# ul_tx_ctrl.net
KiCad netlist of a schematic drawn in Altium Designer
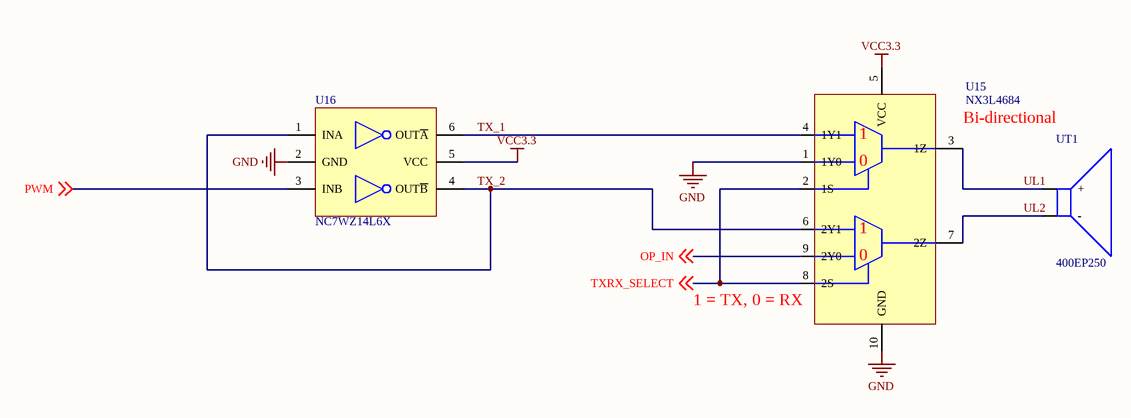
[diagram p0: ul_tx_ctrl.SchDoc]

(export (version "E")
  (design (tool "Eeschema 10.0.6"))
  (components
    (comp (ref "U15")
      (value "NX3L4684")
      (footprint "QFN50P155X200X13-10N")
      (description "IC ANALOG SWITCH SPDT 10XQFN")
      (libsource (lib "opo") (part "NX3L4684"))
    )
    (comp (ref "U16")
      (value "NC7WZ14L6X")
      (footprint "NC7WZ14L6X")
      (description "1 uA supply current, 50 mA output current, Dual inverter")
      (fields (field (name "MFR") "Fairchild Semiconductor"))
      (libsource (lib "opo_general") (part "NC7WZ14L6X"))
    )
    (comp (ref "UT1")
      (value "400EP250")
      (footprint "Transducer recepticle")
      (description "Air Ultrasounic Ceramic Transducers")
      (libsource (lib "opo_general") (part "Tranducer"))
    )
  )
  (nets
    (net (code "1") (name "/TX_1") (class "Default")
      (node (ref "U15") (pin "4") (pinfunction "1Y1_4") (pintype "passive"))
      (node (ref "U16") (pin "6") (pinfunction "OUT~{A}_6") (pintype "passive"))
    )
    (net (code "2") (name "/TX_2") (class "Default")
      (node (ref "U15") (pin "6") (pinfunction "2Y1_6") (pintype "passive"))
      (node (ref "U16") (pin "1") (pinfunction "INA_1") (pintype "passive"))
      (node (ref "U16") (pin "4") (pinfunction "OUT~{B}_4") (pintype "passive"))
    )
    (net (code "3") (name "/UL1") (class "Default")
      (node (ref "U15") (pin "3") (pinfunction "1Z_3") (pintype "passive"))
      (node (ref "UT1") (pin "2") (pinfunction "+_2") (pintype "passive"))
    )
    (net (code "4") (name "/UL2") (class "Default")
      (node (ref "U15") (pin "7") (pinfunction "2Z_7") (pintype "passive"))
      (node (ref "UT1") (pin "1") (pinfunction "-_1") (pintype "passive"))
    )
    (net (code "5") (name "GND") (class "Default")
      (node (ref "U15") (pin "1") (pinfunction "1Y0_1") (pintype "passive"))
      (node (ref "U15") (pin "10") (pinfunction "GND_10") (pintype "passive"))
      (node (ref "U16") (pin "2") (pinfunction "GND_2") (pintype "passive"))
    )
    (net (code "6") (name "OP_IN") (class "Default")
      (node (ref "U15") (pin "9") (pinfunction "2Y0_9") (pintype "passive"))
    )
    (net (code "7") (name "PWM") (class "Default")
      (node (ref "U16") (pin "3") (pinfunction "INB_3") (pintype "passive"))
    )
    (net (code "8") (name "TXRX_SELECT") (class "Default")
      (node (ref "U15") (pin "2") (pinfunction "1S_2") (pintype "passive"))
      (node (ref "U15") (pin "8") (pinfunction "2S_8") (pintype "passive"))
    )
    (net (code "9") (name "VCC3.3") (class "Default")
      (node (ref "U15") (pin "5") (pinfunction "VCC_5") (pintype "passive"))
      (node (ref "U16") (pin "5") (pinfunction "VCC_5") (pintype "passive"))
    )
  )
)
